# DS3231.net
KiCad netlist of a schematic drawn in Altium Designer
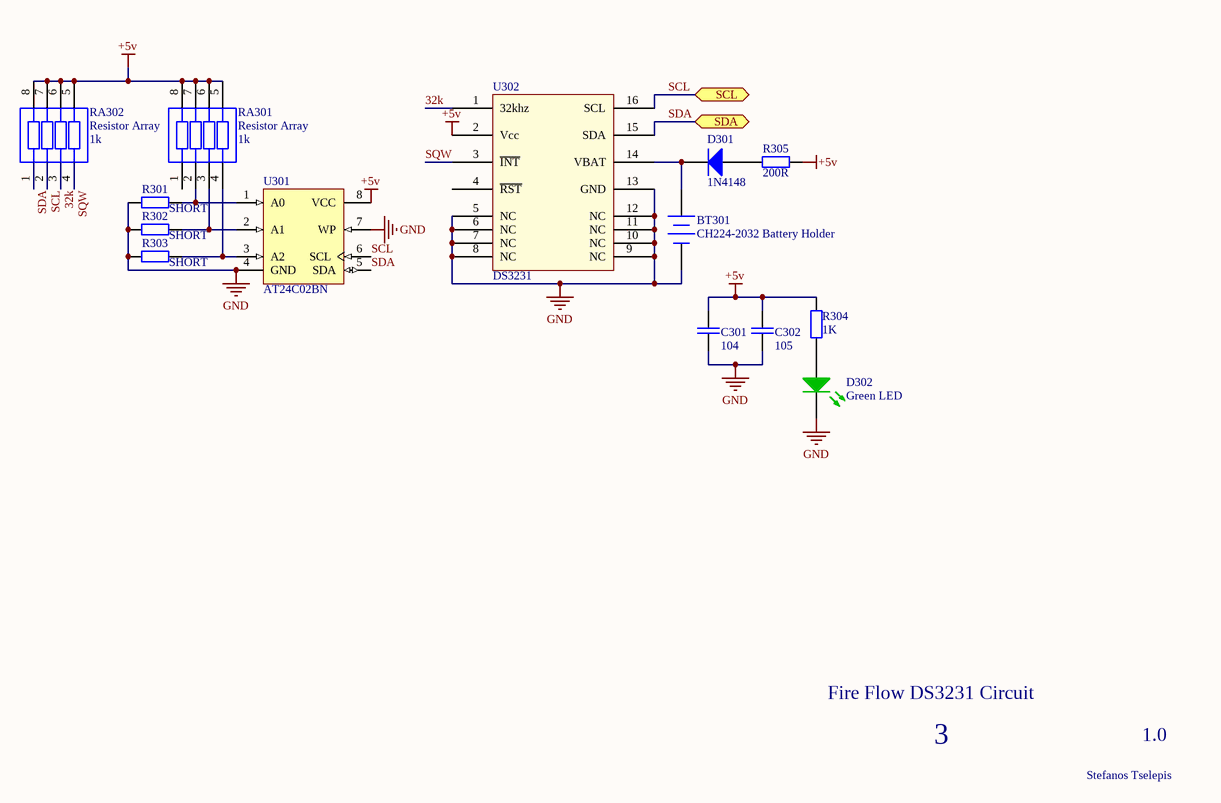
[diagram p0: DS3231.SchDoc]

(export (version "E")
  (design (tool "Eeschema 10.0.6"))
  (components
    (comp (ref "BT301")
      (value "CH224-2032 Battery Holder")
      (footprint "CH224-2032 Battery Holder")
      (description "Multicell Battery")
      (libsource (lib "FireFlow Lib") (part "Battery"))
    )
    (comp (ref "C301")
      (value "104")
      (footprint "CC2013-0805")
      (libsource (lib "FireFlow Lib") (part "Cap Metal Film"))
    )
    (comp (ref "C302")
      (value "105")
      (footprint "CC2013-0805")
      (libsource (lib "FireFlow Lib") (part "Cap Metal Film"))
    )
    (comp (ref "D301")
      (value "1N4148")
      (footprint "CD2012-0805")
      (libsource (lib "FireFlow Lib") (part "Diode"))
    )
    (comp (ref "D302")
      (value "Green LED")
      (footprint "CD3216-1206")
      (description "RED")
      (libsource (lib "FireFlow Lib") (part "LED"))
    )
    (comp (ref "R301")
      (value "SHORT")
      (footprint "CR2012-0805")
      (libsource (lib "FireFlow Lib") (part "Resistor"))
    )
    (comp (ref "R302")
      (value "SHORT")
      (footprint "CR2012-0805")
      (libsource (lib "FireFlow Lib") (part "Resistor"))
    )
    (comp (ref "R303")
      (value "SHORT")
      (footprint "CR2012-0805")
      (libsource (lib "FireFlow Lib") (part "Resistor"))
    )
    (comp (ref "R304") (value "1K") (footprint "CR2012-0805") (libsource (lib "") (part "Resistor_2")))
    (comp (ref "R305") (value "200R") (footprint "CR2012-0805") (libsource (lib "") (part "Resistor_1")))
    (comp (ref "RA301")
      (value "Resistor Array")
      (footprint "EXB38V")
      (fields (field (name "ALTIUM_VALUE") "1k"))
      (libsource (lib "FireFlow Lib") (part "Resistor Array"))
    )
    (comp (ref "RA302")
      (value "Resistor Array")
      (footprint "EXB38V")
      (fields (field (name "ALTIUM_VALUE") "1k"))
      (libsource (lib "FireFlow Lib") (part "Resistor Array"))
    )
    (comp (ref "U301")
      (value "AT24C02BN")
      (footprint "S8")
      (fields (field (name "PUBLISHER") "Altium Limited"))
      (libsource (lib "FireFlow Lib") (part "AT24C02BN-SP25-B"))
    )
    (comp (ref "U302")
      (value "DS3231")
      (footprint "SO-G16/D10.4")
      (libsource (lib "FireFlow Lib") (part "DS3231"))
    )
  )
  (nets
    (net (code "1") (name "+5v") (class "Default")
      (node (ref "C301") (pin "1") (pinfunction "1_1") (pintype "passive"))
      (node (ref "C302") (pin "1") (pinfunction "1_1") (pintype "passive"))
      (node (ref "R304") (pin "1") (pinfunction "1_1") (pintype "passive"))
      (node (ref "R305") (pin "2") (pinfunction "2_2") (pintype "passive"))
      (node (ref "RA301") (pin "5") (pinfunction "5_5") (pintype "passive"))
      (node (ref "RA301") (pin "6") (pinfunction "6_6") (pintype "passive"))
      (node (ref "RA301") (pin "7") (pinfunction "7_7") (pintype "passive"))
      (node (ref "RA301") (pin "8") (pinfunction "8_8") (pintype "passive"))
      (node (ref "RA302") (pin "5") (pinfunction "5_5") (pintype "passive"))
      (node (ref "RA302") (pin "6") (pinfunction "6_6") (pintype "passive"))
      (node (ref "RA302") (pin "7") (pinfunction "7_7") (pintype "passive"))
      (node (ref "RA302") (pin "8") (pinfunction "8_8") (pintype "passive"))
      (node (ref "U301") (pin "8") (pinfunction "VCC_8") (pintype "power_in"))
      (node (ref "U302") (pin "2") (pinfunction "Vcc_2") (pintype "power_in"))
    )
    (net (code "2") (name "/32k") (class "Default")
      (node (ref "RA302") (pin "3") (pinfunction "3_3") (pintype "passive"))
      (node (ref "U302") (pin "1") (pinfunction "32khz_1") (pintype "passive"))
    )
    (net (code "3") (name "/SCL") (class "Default")
      (node (ref "RA302") (pin "2") (pinfunction "2_2") (pintype "passive"))
      (node (ref "U301") (pin "6") (pinfunction "SCL_6") (pintype "input"))
      (node (ref "U302") (pin "16") (pinfunction "SCL_16") (pintype "passive"))
    )
    (net (code "4") (name "/SDA") (class "Default")
      (node (ref "RA302") (pin "1") (pinfunction "1_1") (pintype "passive"))
      (node (ref "U301") (pin "5") (pinfunction "SDA_5") (pintype "bidirectional"))
      (node (ref "U302") (pin "15") (pinfunction "SDA_15") (pintype "passive"))
    )
    (net (code "5") (name "/SQW") (class "Default")
      (node (ref "RA302") (pin "4") (pinfunction "4_4") (pintype "passive"))
      (node (ref "U302") (pin "3") (pinfunction "~{INT}_3") (pintype "passive"))
    )
    (net (code "6") (name "GND") (class "Default")
      (node (ref "BT301") (pin "2") (pinfunction "-_2") (pintype "passive"))
      (node (ref "C301") (pin "2") (pinfunction "2_2") (pintype "passive"))
      (node (ref "C302") (pin "2") (pinfunction "2_2") (pintype "passive"))
      (node (ref "D302") (pin "2") (pinfunction "K_2") (pintype "passive"))
      (node (ref "R301") (pin "2") (pinfunction "2_2") (pintype "passive"))
      (node (ref "R302") (pin "2") (pinfunction "2_2") (pintype "passive"))
      (node (ref "R303") (pin "2") (pinfunction "2_2") (pintype "passive"))
      (node (ref "U301") (pin "4") (pinfunction "GND_4") (pintype "power_in"))
      (node (ref "U301") (pin "7") (pinfunction "WP_7") (pintype "input"))
      (node (ref "U302") (pin "10") (pinfunction "NC_10") (pintype "passive"))
      (node (ref "U302") (pin "11") (pinfunction "NC_11") (pintype "passive"))
      (node (ref "U302") (pin "12") (pinfunction "NC_12") (pintype "passive"))
      (node (ref "U302") (pin "13") (pinfunction "GND_13") (pintype "passive"))
      (node (ref "U302") (pin "5") (pinfunction "NC_5") (pintype "passive"))
      (node (ref "U302") (pin "6") (pinfunction "NC_6") (pintype "passive"))
      (node (ref "U302") (pin "7") (pinfunction "NC_7") (pintype "passive"))
      (node (ref "U302") (pin "8") (pinfunction "NC_8") (pintype "passive"))
      (node (ref "U302") (pin "9") (pinfunction "NC_9") (pintype "passive"))
    )
    (net (code "7") (name "Net-(BT301-+)") (class "Default")
      (node (ref "BT301") (pin "1") (pinfunction "+_1") (pintype "passive"))
      (node (ref "D301") (pin "K") (pinfunction "K_K") (pintype "passive"))
      (node (ref "U302") (pin "14") (pinfunction "VBAT_14") (pintype "passive"))
    )
    (net (code "8") (name "Net-(D301-PadA)") (class "Default")
      (node (ref "D301") (pin "A") (pinfunction "A_A") (pintype "passive"))
      (node (ref "R305") (pin "1") (pinfunction "1_1") (pintype "passive"))
    )
    (net (code "9") (name "Net-(D302-A)") (class "Default")
      (node (ref "D302") (pin "1") (pinfunction "A_1") (pintype "passive"))
      (node (ref "R304") (pin "2") (pinfunction "2_2") (pintype "passive"))
    )
    (net (code "10") (name "Net-(U301-A0)") (class "Default")
      (node (ref "R301") (pin "1") (pinfunction "1_1") (pintype "passive"))
      (node (ref "RA301") (pin "2") (pinfunction "2_2") (pintype "passive"))
      (node (ref "U301") (pin "1") (pinfunction "A0_1") (pintype "input"))
    )
    (net (code "11") (name "Net-(U301-A1)") (class "Default")
      (node (ref "R302") (pin "1") (pinfunction "1_1") (pintype "passive"))
      (node (ref "RA301") (pin "3") (pinfunction "3_3") (pintype "passive"))
      (node (ref "U301") (pin "2") (pinfunction "A1_2") (pintype "input"))
    )
    (net (code "12") (name "Net-(U301-A2)") (class "Default")
      (node (ref "R303") (pin "1") (pinfunction "1_1") (pintype "passive"))
      (node (ref "RA301") (pin "4") (pinfunction "4_4") (pintype "passive"))
      (node (ref "U301") (pin "3") (pinfunction "A2_3") (pintype "input"))
    )
    (net (code "13") (name "unconnected-(RA301-Pad1)") (class "Default")
      (node (ref "RA301") (pin "1") (pinfunction "1_1") (pintype "passive"))
    )
    (net (code "14") (name "unconnected-(U302-~{RST}-Pad4)") (class "Default")
      (node (ref "U302") (pin "4") (pinfunction "~{RST}_4") (pintype "passive"))
    )
  )
)
